# Systolic.net
KiCad netlist of a schematic drawn in Altium Designer
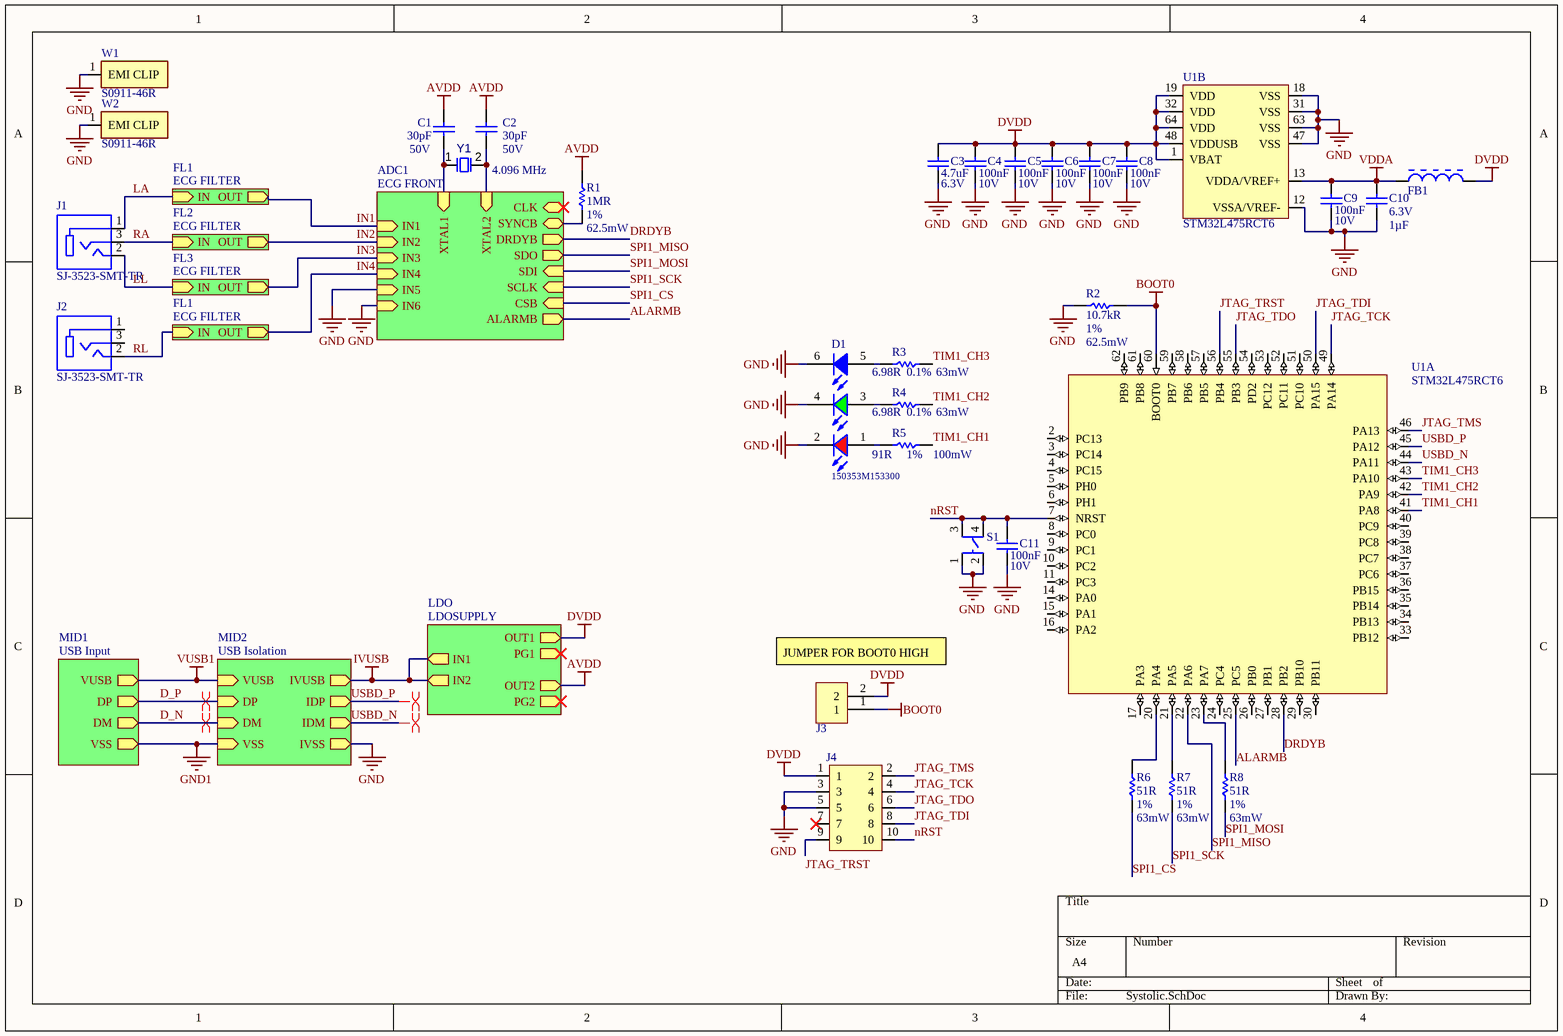
[diagram p0: Systolic.SchDoc]

(export (version "E")
  (design (tool "Eeschema 10.0.6"))
  (components
    (comp (ref "C1")
      (value "MC0402N300J500CT")
      (footprint "0402 CAPACITOR")
      (description "Cap Ceramic 30pF 50V C0G 5% SMD 0402 125°C")
      (fields
        (field (name "CAPACITANCE") "30pF")
        (field (name "VOLTAGE RATING") "50V")
        (field (name "TOLERANCE") "5%")
      )
      (libsource (lib "Premier EDA Student Advantage Programme") (part "Capacitor"))
    )
    (comp (ref "C2")
      (value "MC0402N300J500CT")
      (footprint "0402 CAPACITOR")
      (description "Cap Ceramic 30pF 50V C0G 5% SMD 0402 125°C")
      (fields
        (field (name "CAPACITANCE") "30pF")
        (field (name "VOLTAGE RATING") "50V")
        (field (name "TOLERANCE") "5%")
      )
      (libsource (lib "Premier EDA Student Advantage Programme") (part "Capacitor"))
    )
    (comp (ref "C3")
      (value "CL10A475KQ8NNNC")
      (footprint "0402 CAPACITOR")
      (description "Cap Ceramic 4.7uF 6.3V X5R 10% SMD 0402 85°C")
      (fields
        (field (name "CAPACITANCE") "4.7uF")
        (field (name "VOLTAGE RATING") "6.3V")
        (field (name "VOLTAGE") "6.3V")
        (field (name "TOLERANCE") "10%")
      )
      (libsource (lib "Premier EDA Student Advantage Programme") (part "Capacitor"))
    )
    (comp (ref "C4")
      (value "C0402C104K8PACTU")
      (footprint "0402 CAPACITOR")
      (description "Cap Ceramic 0.1uF 10V X5R 10% SMD 0402 85°C")
      (fields
        (field (name "CAPACITANCE") "100nF")
        (field (name "VOLTAGE RATING") "10V")
        (field (name "VOLTAGE") "10V")
        (field (name "TOLERANCE") "10%")
      )
      (libsource (lib "Premier EDA Student Advantage Programme") (part "Capacitor"))
    )
    (comp (ref "C5")
      (value "C0402C104K8PACTU")
      (footprint "0402 CAPACITOR")
      (description "Cap Ceramic 0.1uF 10V X5R 10% SMD 0402 85°C")
      (fields
        (field (name "CAPACITANCE") "100nF")
        (field (name "VOLTAGE") "10V")
        (field (name "TOLERANCE") "10%")
        (field (name "VOLTAGE RATING") "10V")
      )
      (libsource (lib "Premier EDA Student Advantage Programme") (part "Capacitor"))
    )
    (comp (ref "C6")
      (value "C0402C104K8PACTU")
      (footprint "0402 CAPACITOR")
      (description "Cap Ceramic 0.1uF 10V X5R 10% SMD 0402 85°C")
      (fields
        (field (name "CAPACITANCE") "100nF")
        (field (name "VOLTAGE RATING") "10V")
        (field (name "VOLTAGE") "10V")
        (field (name "TOLERANCE") "10%")
      )
      (libsource (lib "Premier EDA Student Advantage Programme") (part "Capacitor"))
    )
    (comp (ref "C7")
      (value "C0402C104K8PACTU")
      (footprint "0402 CAPACITOR")
      (description "Cap Ceramic 0.1uF 10V X5R 10% SMD 0402 85°C")
      (fields
        (field (name "CAPACITANCE") "100nF")
        (field (name "VOLTAGE RATING") "10V")
        (field (name "VOLTAGE") "10V")
        (field (name "TOLERANCE") "10%")
      )
      (libsource (lib "Premier EDA Student Advantage Programme") (part "Capacitor"))
    )
    (comp (ref "C8")
      (value "C0402C104K8PACTU")
      (footprint "0402 CAPACITOR")
      (description "Cap Ceramic 0.1uF 10V X5R 10% SMD 0402 85°C")
      (fields
        (field (name "CAPACITANCE") "100nF")
        (field (name "VOLTAGE RATING") "10V")
        (field (name "VOLTAGE") "10V")
        (field (name "TOLERANCE") "10%")
      )
      (libsource (lib "Premier EDA Student Advantage Programme") (part "Capacitor"))
    )
    (comp (ref "C9")
      (value "C0402C104K8PACTU")
      (footprint "0402 CAPACITOR")
      (description "Cap Ceramic 0.1uF 10V X5R 10% SMD 0402 85°C")
      (fields
        (field (name "CAPACITANCE") "100nF")
        (field (name "VOLTAGE RATING") "10V")
        (field (name "VOLTAGE") "10V")
        (field (name "TOLERANCE") "10%")
      )
      (libsource (lib "") (part "Capacitor_1"))
    )
    (comp (ref "C10")
      (value "1µF")
      (footprint "0402 CAPACITOR")
      (description "CAP CER 1UF 6.3V 10% X5R 0402")
      (fields
        (field (name "VOLTAGE RATING (DC)") "6.3V")
        (field (name "MANUFACTURER") "KEMET")
        (field (name "MANUFACTURER PART NUMBER") "C0402C105K9PACTU")
      )
      (libsource (lib "Premier EDA Student Advantage Programme") (part "Symbol"))
    )
    (comp (ref "C11")
      (value "C0402C104K8PACTU")
      (footprint "0402 CAPACITOR")
      (description "Cap Ceramic 0.1uF 10V X5R 10% SMD 0402 85°C")
      (fields
        (field (name "CAPACITANCE") "100nF")
        (field (name "VOLTAGE RATING") "10V")
        (field (name "VOLTAGE") "10V")
        (field (name "TOLERANCE") "10%")
      )
      (libsource (lib "Premier EDA Student Advantage Programme") (part "Capacitor"))
    )
    (comp (ref "D1")
      (value "150353M153300")
      (footprint "WL-SFTD_3535")
      (description "WL-SFTD SMT Full-color Top LED Diffused, size 3535, Red & Green & Blue, 120deg")
      (fields (field (name "PUBLISHER") "Wurth Elektronik"))
      (libsource (lib "Premier EDA Student Advantage Programme") (part "150353M153300"))
    )
    (comp (ref "FB1")
      (value "BLM15AX601SN1D")
      (footprint "0402 RESISTOR")
      (description "Ferrite Beads Multi-Layer 600Ohm 25% 100MHz 500mA 340mOhm DCR 0402 T/R")
      (fields (field (name "TOLERANCE") "25%"))
      (libsource (lib "Premier EDA Student Advantage Programme") (part "MURA-FB-2"))
    )
    (comp (ref "J1")
      (value "SJ-3523-SMT-TR")
      (footprint "CUI_SJ-3523-SMT-TR")
      (description "CONN JACK STEREO 3.5MM SMD R/A")
      (fields (field (name "MF") "CUI Devices"))
      (libsource (lib "Premier EDA Student Advantage Programme") (part "SJ-3523-SMT-TR"))
    )
    (comp (ref "J2")
      (value "SJ-3523-SMT-TR")
      (footprint "CUI_SJ-3523-SMT-TR")
      (description "CONN JACK STEREO 3.5MM SMD R/A")
      (fields (field (name "MF") "CUI Devices"))
      (libsource (lib "Premier EDA Student Advantage Programme") (part "SJ-3523-SMT-TR"))
    )
    (comp (ref "J3")
      (value "SAMTEC-TSW-102-07-X-SJ")
      (footprint "SAMTEC-TSW-102-07-X-S")
      (libsource (lib "Premier EDA Student Advantage Programme") (part "SAMTEC-TSW-102-07-X-SJ"))
    )
    (comp (ref "J4")
      (value "FTSH-105-01-L-DV-K-P")
      (footprint "FTSH-105-01-L-DV-K-P")
      (description "TERMINAL STRIP, .050\"(1.27mm) PITCH, 10 PINS, KEYED")
      (fields (field (name "MANUFACTURER") "SAMTEC") (field (name "CREATED") "November 30, 2016 - Wendy Xin"))
      (libsource (lib "Premier EDA Student Advantage Programme") (part "FTSH-105-01-L-DV-K-P"))
    )
    (comp (ref "R1")
      (value "MCWR04X1004FTL")
      (footprint "0402 RESISTOR")
      (description "1MR 0402")
      (fields
        (field (name "RESISTANCE") "1MR")
        (field (name "TOLERANCE") "1%")
        (field (name "POWER RATING") "62.5mW")
      )
      (libsource (lib "Premier EDA Student Advantage Programme") (part "Resistor"))
    )
    (comp (ref "R2")
      (value "MCWR04X1072FTL")
      (footprint "0402 RESISTOR")
      (description "MULTICOMP - MCMR04X24R0FTL - RES, CERAMIC 10.7kR, 1%, 0.063W, 0402")
      (fields
        (field (name "RESISTANCE") "10.7kR")
        (field (name "TOLERANCE") "1%")
        (field (name "POWER RATING") "62.5mW")
      )
      (libsource (lib "Premier EDA Student Advantage Programme") (part "Resistor"))
    )
    (comp (ref "R3")
      (value "RN73C1J6R98BTDF")
      (footprint "0603 RESISTOR")
      (description "RES, THIN FILM 6.98R, 0.1%, 0.063W, 0603")
      (fields
        (field (name "RESISTANCE") "6.98R")
        (field (name "TOLERANCE") "0.1%")
        (field (name "POWER RATING") "63mW")
      )
      (libsource (lib "Premier EDA Student Advantage Programme") (part "Resistor"))
    )
    (comp (ref "R4")
      (value "RN73C1J6R98BTDF")
      (footprint "0603 RESISTOR")
      (description "RES, THIN FILM 6.98R, 0.1%, 0.063W, 0603")
      (fields
        (field (name "RESISTANCE") "6.98R")
        (field (name "TOLERANCE") "0.1%")
        (field (name "POWER RATING") "63mW")
      )
      (libsource (lib "Premier EDA Student Advantage Programme") (part "Resistor"))
    )
    (comp (ref "R5")
      (value "CRCW060391R0FKEA")
      (footprint "0603 RESISTOR")
      (description "RES, THICK FILM 91R, 1%, 0.1W, 0603")
      (fields
        (field (name "RESISTANCE") "91R")
        (field (name "TOLERANCE") "1%")
        (field (name "POWER RATING") "100mW")
      )
      (libsource (lib "Premier EDA Student Advantage Programme") (part "Resistor"))
    )
    (comp (ref "R6")
      (value "CRCW040251R0FKED")
      (footprint "0402 RESISTOR")
      (description "51R 0402 AEC-Q200")
      (fields
        (field (name "RESISTANCE") "51R")
        (field (name "TOLERANCE") "1%")
        (field (name "POWER RATING") "63mW")
      )
      (libsource (lib "Premier EDA Student Advantage Programme") (part "Resistor"))
    )
    (comp (ref "R7")
      (value "CRCW040251R0FKED")
      (footprint "0402 RESISTOR")
      (description "51R 0402 AEC-Q200")
      (fields
        (field (name "RESISTANCE") "51R")
        (field (name "TOLERANCE") "1%")
        (field (name "POWER RATING") "63mW")
      )
      (libsource (lib "Premier EDA Student Advantage Programme") (part "Resistor"))
    )
    (comp (ref "R8")
      (value "CRCW040251R0FKED")
      (footprint "0402 RESISTOR")
      (description "51R 0402 AEC-Q200")
      (fields
        (field (name "RESISTANCE") "51R")
        (field (name "TOLERANCE") "1%")
        (field (name "POWER RATING") "63mW")
      )
      (libsource (lib "Premier EDA Student Advantage Programme") (part "Resistor"))
    )
    (comp (ref "S1")
      (value "TL3305BF260QG")
      (footprint "TL3305BF260QG-Footprint-1")
      (description "Switch Tactile N.O. SPST Round Button Gull Wing 0.05A 12VDC 2.55N SMD T/R")
      (libsource (lib "Premier EDA Student Advantage Programme") (part "KMS221GLFS"))
    )
    (comp (ref "U1")
      (value "STM32L475RCT6")
      (footprint "TSQFP50P1200X1200X160-64N")
      (description "Ultra-low-power with FPU ARM Cortex-M4 MCU 80 MHz with 256 Kbytes Flash, USB OTG")
      (libsource (lib "") (part "STM32L475RCT6_1"))
    )
    (comp (ref "W1")
      (value "S0911-46R")
      (footprint "S0911-46R-Footprint-1")
      (description "Compact RFI Shield Clip Socket Surface Mount Beryllium Copper T/R")
      (libsource (lib "Premier EDA Student Advantage Programme") (part "S0911-46R"))
    )
    (comp (ref "W2")
      (value "S0911-46R")
      (footprint "S0911-46R-Footprint-1")
      (description "Compact RFI Shield Clip Socket Surface Mount Beryllium Copper T/R")
      (libsource (lib "Premier EDA Student Advantage Programme") (part "S0911-46R"))
    )
    (comp (ref "Y1")
      (value "ABLS-4.096MHZ-20-B-4-Y-T")
      (footprint "Crystal")
      (fields (field (name "FREQUENCY") "4.096 MHz"))
      (libsource (lib "Premier EDA Student Advantage Programme") (part "CMP-001-0024-1"))
    )
  )
  (nets
    (net (code "1") (name "/ALARMB") (class "Default")
      (node (ref "U1") (pin "25") (pinfunction "PC5_25") (pintype "bidirectional"))
    )
    (net (code "3") (name "/DRDYB") (class "Default")
      (node (ref "U1") (pin "28") (pinfunction "PB2_28") (pintype "bidirectional"))
    )
    (net (code "10") (name "/JTAG_TCK") (class "Default")
      (node (ref "J4") (pin "4") (pinfunction "4_4") (pintype "power_in"))
      (node (ref "U1") (pin "49") (pinfunction "PA14_49") (pintype "bidirectional"))
    )
    (net (code "11") (name "/JTAG_TDI") (class "Default")
      (node (ref "J4") (pin "8") (pinfunction "8_8") (pintype "power_in"))
      (node (ref "U1") (pin "50") (pinfunction "PA15_50") (pintype "bidirectional"))
    )
    (net (code "12") (name "/JTAG_TDO") (class "Default")
      (node (ref "J4") (pin "6") (pinfunction "6_6") (pintype "power_in"))
      (node (ref "U1") (pin "55") (pinfunction "PB3_55") (pintype "bidirectional"))
    )
    (net (code "13") (name "/JTAG_TMS") (class "Default")
      (node (ref "J4") (pin "2") (pinfunction "2_2") (pintype "power_in"))
      (node (ref "U1") (pin "46") (pinfunction "PA13_46") (pintype "bidirectional"))
    )
    (net (code "14") (name "/JTAG_TRST") (class "Default")
      (node (ref "J4") (pin "9") (pinfunction "9_9") (pintype "power_in"))
      (node (ref "U1") (pin "56") (pinfunction "PB4_56") (pintype "bidirectional"))
    )
    (net (code "15") (name "/LA") (class "Default")
      (node (ref "J1") (pin "1") (pinfunction "1_1") (pintype "passive"))
    )
    (net (code "16") (name "/LL") (class "Default")
      (node (ref "J1") (pin "2") (pinfunction "2_2") (pintype "passive"))
    )
    (net (code "19") (name "/RA") (class "Default")
      (node (ref "J1") (pin "3") (pinfunction "3_3") (pintype "passive"))
    )
    (net (code "20") (name "/RL") (class "Default")
      (node (ref "J2") (pin "2") (pinfunction "2_2") (pintype "passive"))
    )
    (net (code "21") (name "/SPI1_CS") (class "Default")
      (node (ref "R6") (pin "1") (pinfunction "1_1") (pintype "power_in"))
    )
    (net (code "22") (name "/SPI1_MISO") (class "Default")
      (node (ref "U1") (pin "22") (pinfunction "PA6_22") (pintype "bidirectional"))
    )
    (net (code "23") (name "/SPI1_MOSI") (class "Default")
      (node (ref "R8") (pin "1") (pinfunction "1_1") (pintype "power_in"))
    )
    (net (code "24") (name "/SPI1_SCK") (class "Default")
      (node (ref "R7") (pin "1") (pinfunction "1_1") (pintype "power_in"))
    )
    (net (code "25") (name "/SYNCB") (class "Default")
      (node (ref "R1") (pin "2") (pinfunction "2_2") (pintype "power_in"))
    )
    (net (code "26") (name "/TIM1_CH1") (class "Default")
      (node (ref "R5") (pin "2") (pinfunction "2_2") (pintype "power_in"))
      (node (ref "U1") (pin "41") (pinfunction "PA8_41") (pintype "bidirectional"))
    )
    (net (code "27") (name "/TIM1_CH2") (class "Default")
      (node (ref "R4") (pin "2") (pinfunction "2_2") (pintype "power_in"))
      (node (ref "U1") (pin "42") (pinfunction "PA9_42") (pintype "bidirectional"))
    )
    (net (code "28") (name "/TIM1_CH3") (class "Default")
      (node (ref "R3") (pin "2") (pinfunction "2_2") (pintype "power_in"))
      (node (ref "U1") (pin "43") (pinfunction "PA10_43") (pintype "bidirectional"))
    )
    (net (code "29") (name "/USBD_N") (class "Default")
      (node (ref "U1") (pin "44") (pinfunction "PA11_44") (pintype "bidirectional"))
    )
    (net (code "30") (name "/USBD_P") (class "Default")
      (node (ref "U1") (pin "45") (pinfunction "PA12_45") (pintype "bidirectional"))
    )
    (net (code "31") (name "/XTAL1") (class "Default")
      (node (ref "C1") (pin "1") (pinfunction "1_1") (pintype "power_in"))
      (node (ref "Y1") (pin "1") (pinfunction "1_1") (pintype "passive"))
    )
    (net (code "32") (name "/XTAL2") (class "Default")
      (node (ref "C2") (pin "1") (pinfunction "1_1") (pintype "power_in"))
      (node (ref "Y1") (pin "2") (pinfunction "2_2") (pintype "passive"))
    )
    (net (code "33") (name "/nRST") (class "Default")
      (node (ref "C11") (pin "2") (pinfunction "2_2") (pintype "power_in"))
      (node (ref "J4") (pin "10") (pinfunction "10_10") (pintype "power_in"))
      (node (ref "S1") (pin "3") (pinfunction "3_3") (pintype "power_in"))
      (node (ref "S1") (pin "4") (pinfunction "4_4") (pintype "power_in"))
      (node (ref "U1") (pin "7") (pinfunction "NRST_7") (pintype "bidirectional"))
    )
    (net (code "34") (name "AVDD") (class "Default")
      (node (ref "C1") (pin "2") (pinfunction "2_2") (pintype "power_in"))
      (node (ref "C2") (pin "2") (pinfunction "2_2") (pintype "power_in"))
      (node (ref "R1") (pin "1") (pinfunction "1_1") (pintype "power_in"))
    )
    (net (code "35") (name "BOOT0") (class "Default")
      (node (ref "J3") (pin "1") (pinfunction "1_1") (pintype "power_in"))
      (node (ref "R2") (pin "2") (pinfunction "2_2") (pintype "power_in"))
      (node (ref "U1") (pin "60") (pinfunction "BOOT0_60") (pintype "input"))
    )
    (net (code "36") (name "DVDD") (class "Default")
      (node (ref "C3") (pin "2") (pinfunction "2_2") (pintype "power_in"))
      (node (ref "C4") (pin "2") (pinfunction "2_2") (pintype "power_in"))
      (node (ref "C5") (pin "2") (pinfunction "2_2") (pintype "power_in"))
      (node (ref "C6") (pin "2") (pinfunction "2_2") (pintype "power_in"))
      (node (ref "C7") (pin "2") (pinfunction "2_2") (pintype "power_in"))
      (node (ref "C8") (pin "2") (pinfunction "2_2") (pintype "power_in"))
      (node (ref "FB1") (pin "2") (pinfunction "2_2") (pintype "passive"))
      (node (ref "J3") (pin "2") (pinfunction "2_2") (pintype "power_in"))
      (node (ref "J4") (pin "1") (pinfunction "1_1") (pintype "power_in"))
      (node (ref "U1") (pin "1") (pinfunction "VBAT_1") (pintype "power_in"))
      (node (ref "U1") (pin "19") (pinfunction "VDD_19") (pintype "power_in"))
      (node (ref "U1") (pin "32") (pinfunction "VDD_32") (pintype "power_in"))
      (node (ref "U1") (pin "48") (pinfunction "VDDUSB_48") (pintype "power_in"))
      (node (ref "U1") (pin "64") (pinfunction "VDD_64") (pintype "power_in"))
    )
    (net (code "37") (name "GND") (class "Default")
      (node (ref "C10") (pin "1") (pintype "power_in"))
      (node (ref "C11") (pin "1") (pinfunction "1_1") (pintype "power_in"))
      (node (ref "C3") (pin "1") (pinfunction "1_1") (pintype "power_in"))
      (node (ref "C4") (pin "1") (pinfunction "1_1") (pintype "power_in"))
      (node (ref "C5") (pin "1") (pinfunction "1_1") (pintype "power_in"))
      (node (ref "C6") (pin "1") (pinfunction "1_1") (pintype "power_in"))
      (node (ref "C7") (pin "1") (pinfunction "1_1") (pintype "power_in"))
      (node (ref "C8") (pin "1") (pinfunction "1_1") (pintype "power_in"))
      (node (ref "C9") (pin "1") (pinfunction "1_1") (pintype "power_in"))
      (node (ref "D1") (pin "2") (pinfunction "K_2") (pintype "passive"))
      (node (ref "D1") (pin "4") (pinfunction "K_4") (pintype "passive"))
      (node (ref "D1") (pin "6") (pinfunction "K_6") (pintype "passive"))
      (node (ref "J4") (pin "3") (pinfunction "3_3") (pintype "power_in"))
      (node (ref "J4") (pin "5") (pinfunction "5_5") (pintype "power_in"))
      (node (ref "R2") (pin "1") (pinfunction "1_1") (pintype "power_in"))
      (node (ref "S1") (pin "1") (pinfunction "1_1") (pintype "power_in"))
      (node (ref "S1") (pin "2") (pinfunction "2_2") (pintype "power_in"))
      (node (ref "U1") (pin "12") (pinfunction "VSSA/VREF-_12") (pintype "power_in"))
      (node (ref "U1") (pin "18") (pinfunction "VSS_18") (pintype "power_in"))
      (node (ref "U1") (pin "31") (pinfunction "VSS_31") (pintype "power_in"))
      (node (ref "U1") (pin "47") (pinfunction "VSS_47") (pintype "power_in"))
      (node (ref "U1") (pin "63") (pinfunction "VSS_63") (pintype "power_in"))
      (node (ref "W1") (pin "1") (pinfunction "EMI_CLIP_1") (pintype "passive"))
      (node (ref "W2") (pin "1") (pinfunction "EMI_CLIP_1") (pintype "passive"))
    )
    (net (code "40") (name "Net-(D1-A-Pad1)") (class "Default")
      (node (ref "D1") (pin "1") (pinfunction "A_1") (pintype "passive"))
      (node (ref "R5") (pin "1") (pinfunction "1_1") (pintype "power_in"))
    )
    (net (code "41") (name "Net-(D1-A-Pad3)") (class "Default")
      (node (ref "D1") (pin "3") (pinfunction "A_3") (pintype "passive"))
      (node (ref "R4") (pin "1") (pinfunction "1_1") (pintype "power_in"))
    )
    (net (code "42") (name "Net-(D1-A-Pad5)") (class "Default")
      (node (ref "D1") (pin "5") (pinfunction "A_5") (pintype "passive"))
      (node (ref "R3") (pin "1") (pinfunction "1_1") (pintype "power_in"))
    )
    (net (code "43") (name "Net-(U1A-PA4)") (class "Default")
      (node (ref "R6") (pin "2") (pinfunction "2_2") (pintype "power_in"))
      (node (ref "U1") (pin "20") (pinfunction "PA4_20") (pintype "bidirectional"))
    )
    (net (code "44") (name "Net-(U1A-PA5)") (class "Default")
      (node (ref "R7") (pin "2") (pinfunction "2_2") (pintype "power_in"))
      (node (ref "U1") (pin "21") (pinfunction "PA5_21") (pintype "bidirectional"))
    )
    (net (code "45") (name "Net-(U1A-PA7)") (class "Default")
      (node (ref "R8") (pin "2") (pinfunction "2_2") (pintype "power_in"))
      (node (ref "U1") (pin "23") (pinfunction "PA7_23") (pintype "bidirectional"))
    )
    (net (code "46") (name "VDDA") (class "Default")
      (node (ref "C10") (pin "2") (pintype "power_in"))
      (node (ref "C9") (pin "2") (pinfunction "2_2") (pintype "power_in"))
      (node (ref "FB1") (pin "1") (pinfunction "1_1") (pintype "passive"))
      (node (ref "U1") (pin "13") (pinfunction "VDDA/VREF+_13") (pintype "power_in"))
    )
    (net (code "48") (name "unconnected-(J2-Pad1)") (class "Default")
      (node (ref "J2") (pin "1") (pinfunction "1_1") (pintype "passive"))
    )
    (net (code "49") (name "unconnected-(J2-Pad3)") (class "Default")
      (node (ref "J2") (pin "3") (pinfunction "3_3") (pintype "passive"))
    )
    (net (code "50") (name "unconnected-(J4-Pad7)") (class "Default")
      (node (ref "J4") (pin "7") (pinfunction "7_7") (pintype "power_in+no_connect"))
    )
    (net (code "51") (name "unconnected-(U1A-PA0-Pad14)") (class "Default")
      (node (ref "U1") (pin "14") (pinfunction "PA0_14") (pintype "bidirectional"))
    )
    (net (code "52") (name "unconnected-(U1A-PA1-Pad15)") (class "Default")
      (node (ref "U1") (pin "15") (pinfunction "PA1_15") (pintype "bidirectional"))
    )
    (net (code "53") (name "unconnected-(U1A-PA2-Pad16)") (class "Default")
      (node (ref "U1") (pin "16") (pinfunction "PA2_16") (pintype "bidirectional"))
    )
    (net (code "54") (name "unconnected-(U1A-PA3-Pad17)") (class "Default")
      (node (ref "U1") (pin "17") (pinfunction "PA3_17") (pintype "bidirectional"))
    )
    (net (code "55") (name "unconnected-(U1A-PB0-Pad26)") (class "Default")
      (node (ref "U1") (pin "26") (pinfunction "PB0_26") (pintype "bidirectional"))
    )
    (net (code "56") (name "unconnected-(U1A-PB1-Pad27)") (class "Default")
      (node (ref "U1") (pin "27") (pinfunction "PB1_27") (pintype "bidirectional"))
    )
    (net (code "57") (name "unconnected-(U1A-PB5-Pad57)") (class "Default")
      (node (ref "U1") (pin "57") (pinfunction "PB5_57") (pintype "bidirectional"))
    )
    (net (code "58") (name "unconnected-(U1A-PB6-Pad58)") (class "Default")
      (node (ref "U1") (pin "58") (pinfunction "PB6_58") (pintype "bidirectional"))
    )
    (net (code "59") (name "unconnected-(U1A-PB7-Pad59)") (class "Default")
      (node (ref "U1") (pin "59") (pinfunction "PB7_59") (pintype "bidirectional"))
    )
    (net (code "60") (name "unconnected-(U1A-PB8-Pad61)") (class "Default")
      (node (ref "U1") (pin "61") (pinfunction "PB8_61") (pintype "bidirectional"))
    )
    (net (code "61") (name "unconnected-(U1A-PB9-Pad62)") (class "Default")
      (node (ref "U1") (pin "62") (pinfunction "PB9_62") (pintype "bidirectional"))
    )
    (net (code "62") (name "unconnected-(U1A-PB10-Pad29)") (class "Default")
      (node (ref "U1") (pin "29") (pinfunction "PB10_29") (pintype "bidirectional"))
    )
    (net (code "63") (name "unconnected-(U1A-PB11-Pad30)") (class "Default")
      (node (ref "U1") (pin "30") (pinfunction "PB11_30") (pintype "bidirectional"))
    )
    (net (code "64") (name "unconnected-(U1A-PB12-Pad33)") (class "Default")
      (node (ref "U1") (pin "33") (pinfunction "PB12_33") (pintype "bidirectional"))
    )
    (net (code "65") (name "unconnected-(U1A-PB13-Pad34)") (class "Default")
      (node (ref "U1") (pin "34") (pinfunction "PB13_34") (pintype "bidirectional"))
    )
    (net (code "66") (name "unconnected-(U1A-PB14-Pad35)") (class "Default")
      (node (ref "U1") (pin "35") (pinfunction "PB14_35") (pintype "bidirectional"))
    )
    (net (code "67") (name "unconnected-(U1A-PB15-Pad36)") (class "Default")
      (node (ref "U1") (pin "36") (pinfunction "PB15_36") (pintype "bidirectional"))
    )
    (net (code "68") (name "unconnected-(U1A-PC0-Pad8)") (class "Default")
      (node (ref "U1") (pin "8") (pinfunction "PC0_8") (pintype "bidirectional"))
    )
    (net (code "69") (name "unconnected-(U1A-PC1-Pad9)") (class "Default")
      (node (ref "U1") (pin "9") (pinfunction "PC1_9") (pintype "bidirectional"))
    )
    (net (code "70") (name "unconnected-(U1A-PC2-Pad10)") (class "Default")
      (node (ref "U1") (pin "10") (pinfunction "PC2_10") (pintype "bidirectional"))
    )
    (net (code "71") (name "unconnected-(U1A-PC3-Pad11)") (class "Default")
      (node (ref "U1") (pin "11") (pinfunction "PC3_11") (pintype "bidirectional"))
    )
    (net (code "72") (name "unconnected-(U1A-PC4-Pad24)") (class "Default")
      (node (ref "U1") (pin "24") (pinfunction "PC4_24") (pintype "bidirectional"))
    )
    (net (code "73") (name "unconnected-(U1A-PC6-Pad37)") (class "Default")
      (node (ref "U1") (pin "37") (pinfunction "PC6_37") (pintype "bidirectional"))
    )
    (net (code "74") (name "unconnected-(U1A-PC7-Pad38)") (class "Default")
      (node (ref "U1") (pin "38") (pinfunction "PC7_38") (pintype "bidirectional"))
    )
    (net (code "75") (name "unconnected-(U1A-PC8-Pad39)") (class "Default")
      (node (ref "U1") (pin "39") (pinfunction "PC8_39") (pintype "bidirectional"))
    )
    (net (code "76") (name "unconnected-(U1A-PC9-Pad40)") (class "Default")
      (node (ref "U1") (pin "40") (pinfunction "PC9_40") (pintype "bidirectional"))
    )
    (net (code "77") (name "unconnected-(U1A-PC10-Pad51)") (class "Default")
      (node (ref "U1") (pin "51") (pinfunction "PC10_51") (pintype "bidirectional"))
    )
    (net (code "78") (name "unconnected-(U1A-PC11-Pad52)") (class "Default")
      (node (ref "U1") (pin "52") (pinfunction "PC11_52") (pintype "bidirectional"))
    )
    (net (code "79") (name "unconnected-(U1A-PC12-Pad53)") (class "Default")
      (node (ref "U1") (pin "53") (pinfunction "PC12_53") (pintype "bidirectional"))
    )
    (net (code "80") (name "unconnected-(U1A-PC13-Pad2)") (class "Default")
      (node (ref "U1") (pin "2") (pinfunction "PC13_2") (pintype "bidirectional"))
    )
    (net (code "81") (name "unconnected-(U1A-PC14-Pad3)") (class "Default")
      (node (ref "U1") (pin "3") (pinfunction "PC14_3") (pintype "bidirectional"))
    )
    (net (code "82") (name "unconnected-(U1A-PC15-Pad4)") (class "Default")
      (node (ref "U1") (pin "4") (pinfunction "PC15_4") (pintype "bidirectional"))
    )
    (net (code "83") (name "unconnected-(U1A-PD2-Pad54)") (class "Default")
      (node (ref "U1") (pin "54") (pinfunction "PD2_54") (pintype "bidirectional"))
    )
    (net (code "84") (name "unconnected-(U1A-PH0-Pad5)") (class "Default")
      (node (ref "U1") (pin "5") (pinfunction "PH0_5") (pintype "bidirectional"))
    )
    (net (code "85") (name "unconnected-(U1A-PH1-Pad6)") (class "Default")
      (node (ref "U1") (pin "6") (pinfunction "PH1_6") (pintype "bidirectional"))
    )
  )
)
